# RiskChemi_Sensors_V2_11.net
KiCad netlist of a schematic drawn in Altium Designer
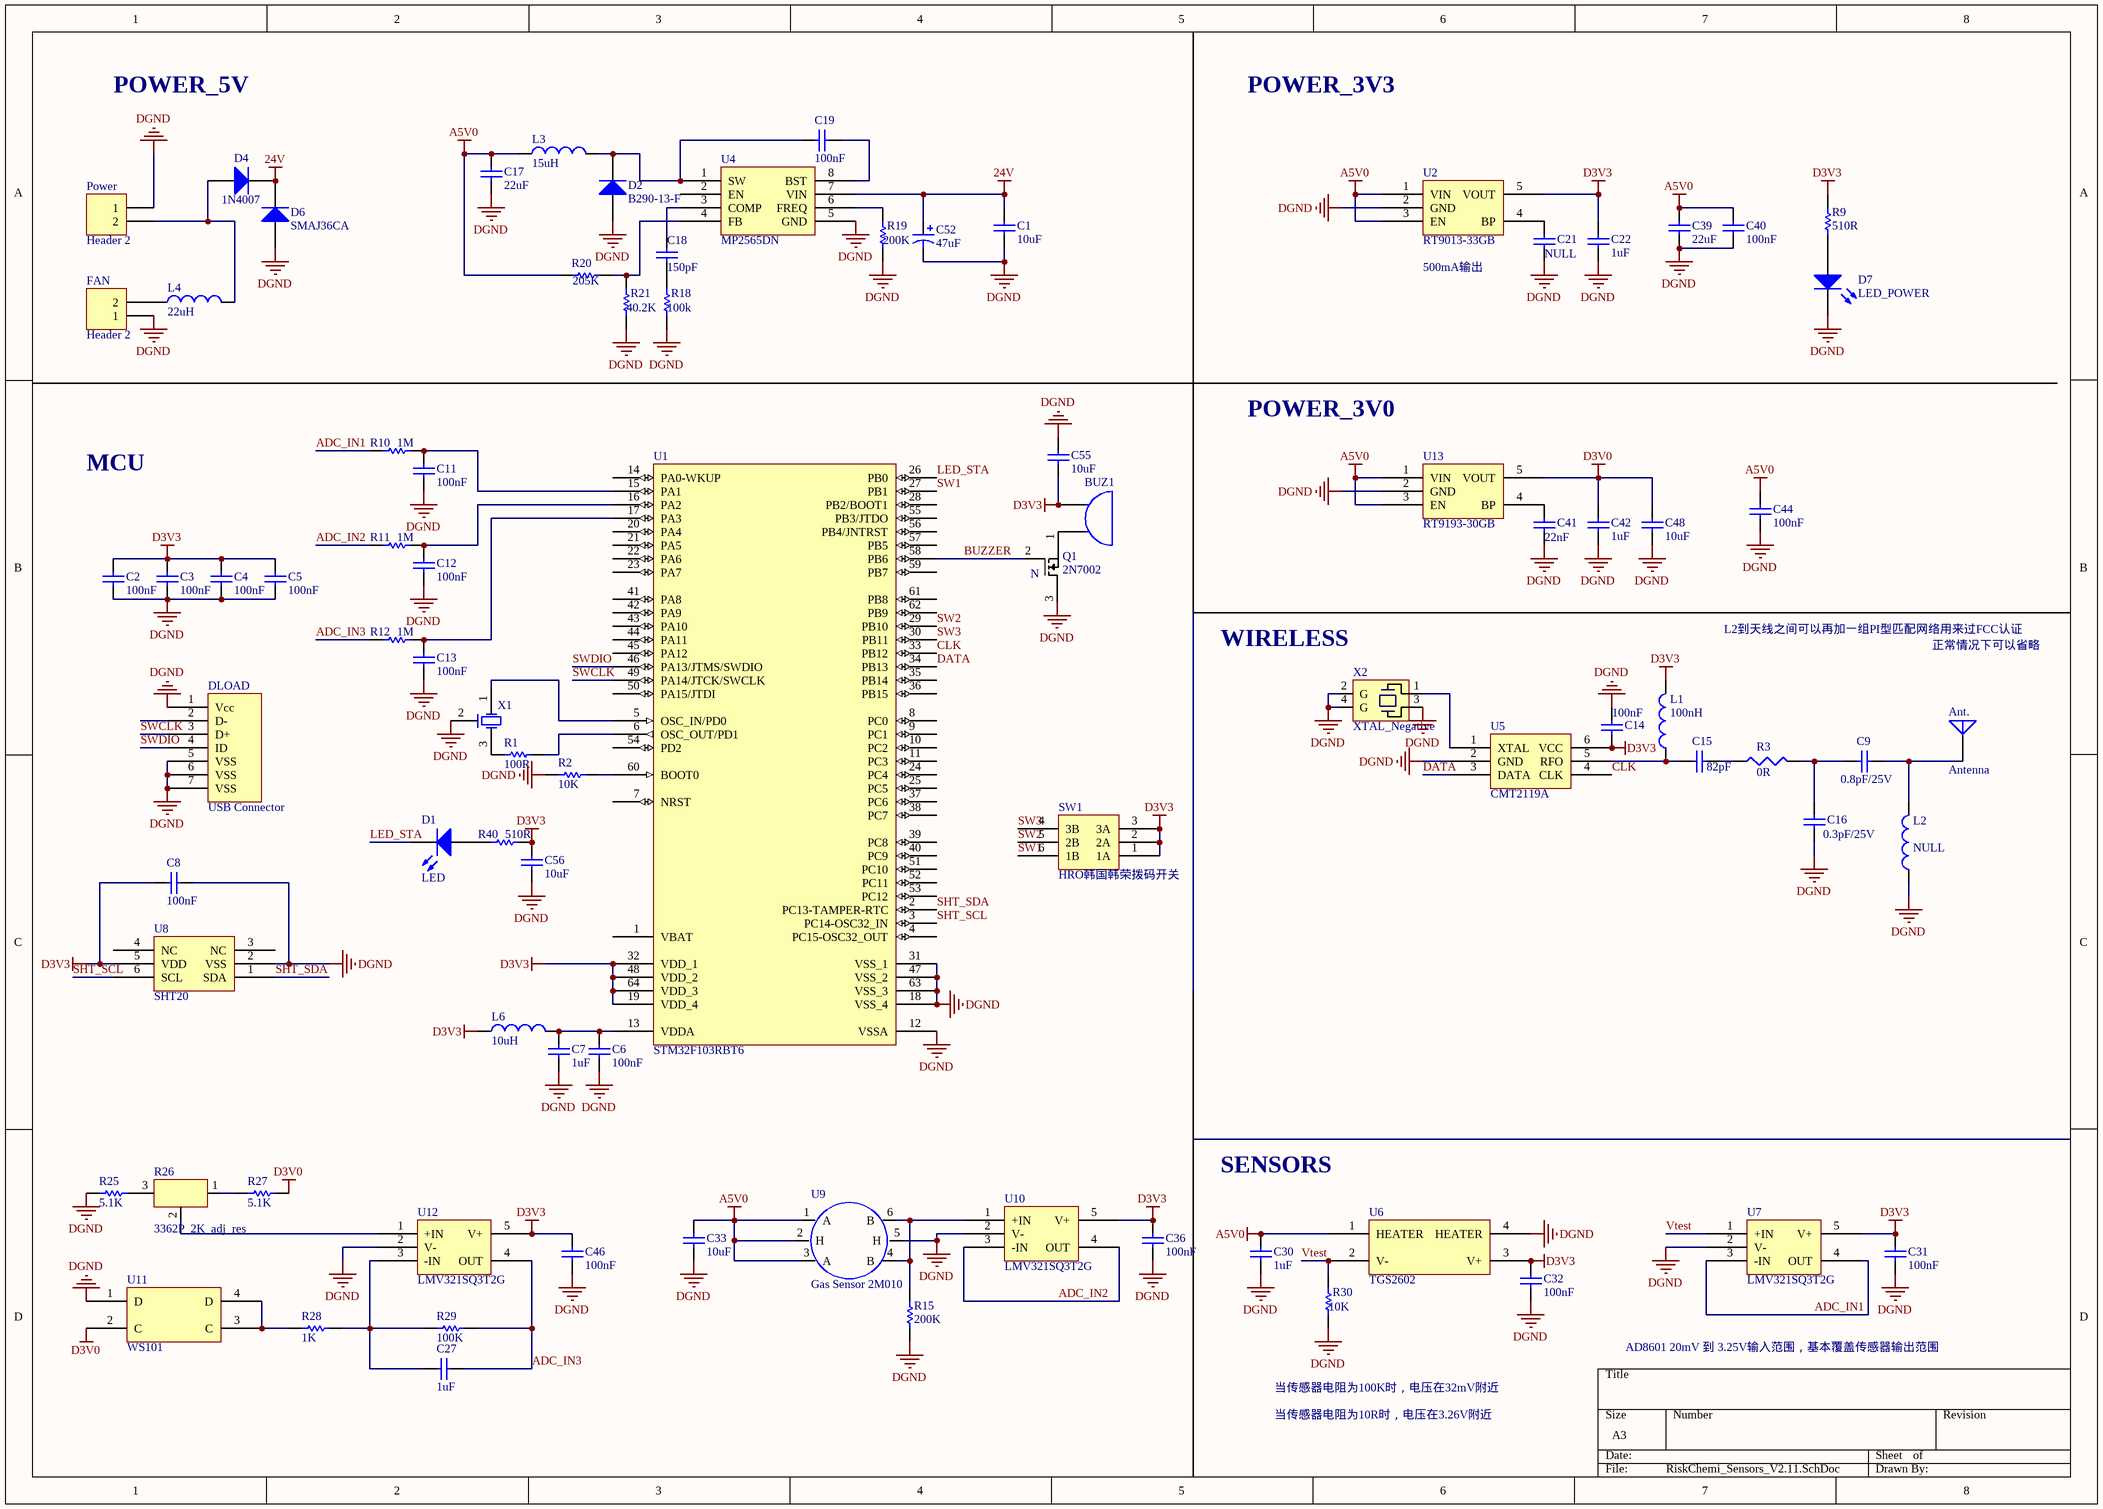
[diagram p0: RiskChemi_Sensors_V2.11.SchDoc]

(export (version "E")
  (design (tool "Eeschema 10.0.6"))
  (components
    (comp (ref "Ant.")
      (value "Antenna")
      (footprint "PIN1")
      (description "Generic Antenna")
      (fields (field (name "PUBLISHER") "Altium Limited"))
      (libsource (lib "Miscellaneous Devices") (part "Antenna"))
    )
    (comp (ref "BUZ1")
      (value "BUZZER 0905 through hole")
      (footprint "BUZ0905")
      (description "Buzzer")
      (libsource (lib "杂元件库") (part "BUZZER"))
    )
    (comp (ref "C1")
      (value "10uF")
      (footprint "0805")
      (description "Capacitor,50V")
      (fields (field (name "PUBLISHER") "Altium Limited"))
      (libsource (lib "Miscellaneous Devices") (part "Cap"))
    )
    (comp (ref "C2")
      (value "100nF")
      (footprint "BinFeng:0603")
      (description "Capacitor")
      (fields (field (name "PUBLISHER") "Altium Limited"))
      (libsource (lib "Miscellaneous Devices") (part "Cap"))
    )
    (comp (ref "C3")
      (value "100nF")
      (footprint "BinFeng:0603")
      (description "Capacitor")
      (fields (field (name "PUBLISHER") "Altium Limited"))
      (libsource (lib "Miscellaneous Devices") (part "Cap"))
    )
    (comp (ref "C4")
      (value "100nF")
      (footprint "BinFeng:0603")
      (description "Capacitor")
      (fields (field (name "PUBLISHER") "Altium Limited"))
      (libsource (lib "Miscellaneous Devices") (part "Cap"))
    )
    (comp (ref "C5")
      (value "100nF")
      (footprint "BinFeng:0603")
      (description "Capacitor")
      (fields (field (name "PUBLISHER") "Altium Limited"))
      (libsource (lib "Miscellaneous Devices") (part "Cap"))
    )
    (comp (ref "C6")
      (value "100nF")
      (footprint "BinFeng:0603")
      (description "Capacitor")
      (fields (field (name "PUBLISHER") "Altium Limited"))
      (libsource (lib "Miscellaneous Devices") (part "Cap"))
    )
    (comp (ref "C7")
      (value "1uF")
      (footprint "BinFeng:0603")
      (description "Capacitor")
      (fields (field (name "PUBLISHER") "Altium Limited"))
      (libsource (lib "Miscellaneous Devices") (part "Cap"))
    )
    (comp (ref "C8")
      (value "100nF")
      (footprint "BinFeng:0603")
      (description "Capacitor")
      (fields (field (name "PUBLISHER") "Altium Limited"))
      (libsource (lib "Miscellaneous Devices") (part "Cap"))
    )
    (comp (ref "C9")
      (value "0.8pF/25V")
      (footprint "1608[0603]")
      (description "Capacitor (Semiconductor SIM Model)")
      (fields (field (name "PUBLISHER") "Altium Limited"))
      (libsource (lib "Miscellaneous Devices") (part "Cap Semi"))
    )
    (comp (ref "C11")
      (value "100nF")
      (footprint "BinFeng:0603")
      (description "Capacitor")
      (fields (field (name "PUBLISHER") "Altium Limited"))
      (libsource (lib "Miscellaneous Devices") (part "Cap"))
    )
    (comp (ref "C12")
      (value "100nF")
      (footprint "BinFeng:0603")
      (description "Capacitor")
      (fields (field (name "PUBLISHER") "Altium Limited"))
      (libsource (lib "Miscellaneous Devices") (part "Cap"))
    )
    (comp (ref "C13")
      (value "100nF")
      (footprint "BinFeng:0603")
      (description "Capacitor")
      (fields (field (name "PUBLISHER") "Altium Limited"))
      (libsource (lib "Miscellaneous Devices") (part "Cap"))
    )
    (comp (ref "C14")
      (value "100nF")
      (footprint "BinFeng:0402")
      (description "Capacitor")
      (fields (field (name "PUBLISHER") "Altium Limited"))
      (libsource (lib "Miscellaneous Devices") (part "Cap"))
    )
    (comp (ref "C15")
      (value "82pF")
      (footprint "BinFeng:0402")
      (description "Capacitor")
      (fields (field (name "PUBLISHER") "Altium Limited"))
      (libsource (lib "Miscellaneous Devices") (part "Cap"))
    )
    (comp (ref "C16")
      (value "0.3pF/25V")
      (footprint "BinFeng:0402")
      (description "Capacitor")
      (fields (field (name "PUBLISHER") "Altium Limited"))
      (libsource (lib "Miscellaneous Devices") (part "Cap"))
    )
    (comp (ref "C17")
      (value "22uF")
      (footprint "0805")
      (description "Capacitor,50V")
      (fields (field (name "PUBLISHER") "Altium Limited"))
      (libsource (lib "Miscellaneous Devices") (part "Cap"))
    )
    (comp (ref "C18")
      (value "150pF")
      (footprint "BinFeng:0603")
      (description "Capacitor")
      (fields (field (name "PUBLISHER") "Altium Limited"))
      (libsource (lib "Miscellaneous Devices") (part "Cap"))
    )
    (comp (ref "C19")
      (value "100nF")
      (footprint "BinFeng:0603")
      (description "Capacitor")
      (fields (field (name "PUBLISHER") "Altium Limited"))
      (libsource (lib "Miscellaneous Devices") (part "Cap"))
    )
    (comp (ref "C21")
      (value "NULL")
      (footprint "BinFeng:0402")
      (description "Capacitor")
      (fields (field (name "PUBLISHER") "Altium Limited"))
      (libsource (lib "Miscellaneous Devices") (part "Cap"))
    )
    (comp (ref "C22")
      (value "1uF")
      (footprint "BinFeng:0402")
      (description "Capacitor")
      (fields (field (name "PUBLISHER") "Altium Limited"))
      (libsource (lib "Miscellaneous Devices") (part "Cap"))
    )
    (comp (ref "C27")
      (value "1uF")
      (footprint "BinFeng:0603")
      (description "Capacitor")
      (fields (field (name "PUBLISHER") "Altium Limited"))
      (libsource (lib "Miscellaneous Devices") (part "Cap"))
    )
    (comp (ref "C30")
      (value "1uF")
      (footprint "BinFeng:0603")
      (description "Capacitor")
      (fields (field (name "PUBLISHER") "Altium Limited"))
      (libsource (lib "Miscellaneous Devices") (part "Cap"))
    )
    (comp (ref "C31")
      (value "100nF")
      (footprint "BinFeng:0603")
      (description "Capacitor")
      (fields (field (name "PUBLISHER") "Altium Limited"))
      (libsource (lib "Miscellaneous Devices") (part "Cap"))
    )
    (comp (ref "C32")
      (value "100nF")
      (footprint "BinFeng:0603")
      (description "Capacitor")
      (fields (field (name "PUBLISHER") "Altium Limited"))
      (libsource (lib "Miscellaneous Devices") (part "Cap"))
    )
    (comp (ref "C33")
      (value "10uF")
      (footprint "0805")
      (description "Capacitor")
      (fields (field (name "PUBLISHER") "Altium Limited"))
      (libsource (lib "Miscellaneous Devices") (part "Cap"))
    )
    (comp (ref "C36")
      (value "100nF")
      (footprint "BinFeng:0603")
      (description "Capacitor")
      (fields (field (name "PUBLISHER") "Altium Limited"))
      (libsource (lib "Miscellaneous Devices") (part "Cap"))
    )
    (comp (ref "C39")
      (value "22uF")
      (footprint "1206")
      (description "Capacitor")
      (fields (field (name "PUBLISHER") "Altium Limited"))
      (libsource (lib "Miscellaneous Devices") (part "Cap"))
    )
    (comp (ref "C40")
      (value "100nF")
      (footprint "BinFeng:0402")
      (description "Capacitor")
      (fields (field (name "PUBLISHER") "Altium Limited"))
      (libsource (lib "Miscellaneous Devices") (part "Cap"))
    )
    (comp (ref "C41")
      (value "22nF")
      (footprint "BinFeng:0402")
      (description "Capacitor")
      (fields (field (name "PUBLISHER") "Altium Limited"))
      (libsource (lib "Miscellaneous Devices") (part "Cap"))
    )
    (comp (ref "C42")
      (value "1uF")
      (footprint "BinFeng:0402")
      (description "Capacitor")
      (fields (field (name "PUBLISHER") "Altium Limited"))
      (libsource (lib "Miscellaneous Devices") (part "Cap"))
    )
    (comp (ref "C44")
      (value "100nF")
      (footprint "BinFeng:0402")
      (description "Capacitor")
      (fields (field (name "PUBLISHER") "Altium Limited"))
      (libsource (lib "Miscellaneous Devices") (part "Cap"))
    )
    (comp (ref "C46")
      (value "100nF")
      (footprint "BinFeng:0603")
      (description "Capacitor")
      (fields (field (name "PUBLISHER") "Altium Limited"))
      (libsource (lib "Miscellaneous Devices") (part "Cap"))
    )
    (comp (ref "C48")
      (value "10uF")
      (footprint "0805")
      (description "Capacitor")
      (fields (field (name "PUBLISHER") "Altium Limited"))
      (libsource (lib "Miscellaneous Devices") (part "Cap"))
    )
    (comp (ref "C52")
      (value "47uF")
      (footprint "cap_pol_8*10.2")
      (description "Polarized Capacitor (Radial)")
      (fields (field (name "PUBLISHER") "Altium Limited"))
      (libsource (lib "Miscellaneous Devices") (part "Cap Pol1"))
    )
    (comp (ref "C55")
      (value "10uF")
      (footprint "0805")
      (description "Capacitor")
      (fields (field (name "PUBLISHER") "Altium Limited"))
      (libsource (lib "Miscellaneous Devices") (part "Cap"))
    )
    (comp (ref "C56")
      (value "10uF")
      (footprint "0805")
      (description "Capacitor")
      (fields (field (name "PUBLISHER") "Altium Limited"))
      (libsource (lib "Miscellaneous Devices") (part "Cap"))
    )
    (comp (ref "D1")
      (value "LED")
      (footprint "1206_LED")
      (description "Typical INFRARED GaAs LED")
      (fields (field (name "PUBLISHER") "Altium Limited"))
      (libsource (lib "Miscellaneous Devices") (part "LED0"))
    )
    (comp (ref "D2")
      (value "B290-13-F")
      (footprint "B290")
      (description "Default Diode")
      (fields (field (name "PUBLISHER") "Altium Limited"))
      (libsource (lib "Miscellaneous Devices") (part "Diode"))
    )
    (comp (ref "D4")
      (value "1N4007")
      (footprint "6032_pol")
      (description "1 Amp General Purpose Rectifier")
      (fields (field (name "PUBLISHER") "Altium Limited"))
      (libsource (lib "Miscellaneous Devices") (part "Diode 1N4007"))
    )
    (comp (ref "D6")
      (value "SMAJ36CA")
      (footprint "B290")
      (description "1 Amp General Purpose Rectifier")
      (fields (field (name "PUBLISHER") "Altium Limited"))
      (libsource (lib "Miscellaneous Devices") (part "Diode 1N4007"))
    )
    (comp (ref "D7")
      (value "LED_POWER")
      (footprint "1206_LED")
      (description "Typical INFRARED GaAs LED")
      (fields (field (name "PUBLISHER") "Altium Limited"))
      (libsource (lib "Miscellaneous Devices") (part "LED0"))
    )
    (comp (ref "DLOAD")
      (value "USB Connector")
      (footprint "Mini_USB")
      (libsource (lib "BinFeng_Connectors") (part "Component_1"))
    )
    (comp (ref "FAN")
      (value "Header 2")
      (footprint "HDR1X2")
      (description "Header, 2-Pin")
      (fields (field (name "PUBLISHER") "Altium Limited"))
      (libsource (lib "") (part "Header 2_1"))
    )
    (comp (ref "L1")
      (value "100nH")
      (footprint "0603C")
      (description "Inductor")
      (fields (field (name "PUBLISHER") "Altium Limited"))
      (libsource (lib "Miscellaneous Devices") (part "Inductor"))
    )
    (comp (ref "L2")
      (value "NULL")
      (footprint "hg:0402")
      (description "Inductor")
      (fields (field (name "PUBLISHER") "Altium Limited"))
      (libsource (lib "Miscellaneous Devices") (part "Inductor"))
    )
    (comp (ref "L3")
      (value "15uH")
      (footprint "4*4 Inductor")
      (description "Inductor, 1A")
      (fields (field (name "PUBLISHER") "Altium Limited"))
      (libsource (lib "Miscellaneous Devices") (part "Inductor"))
    )
    (comp (ref "L4")
      (value "22uH")
      (footprint "10*10Inductor")
      (description "Inductor, 1A")
      (fields (field (name "PUBLISHER") "Altium Limited"))
      (libsource (lib "Miscellaneous Devices") (part "Inductor"))
    )
    (comp (ref "L6")
      (value "10uH")
      (footprint "0805")
      (description "Inductor")
      (fields (field (name "PUBLISHER") "Altium Limited"))
      (libsource (lib "Miscellaneous Devices") (part "Inductor"))
    )
    (comp (ref "Power")
      (value "Header 2")
      (footprint "HDR1X2")
      (description "Header, 2-Pin")
      (fields (field (name "PUBLISHER") "Altium Limited"))
      (libsource (lib "Miscellaneous Connectors") (part "Header 2"))
    )
    (comp (ref "Q1") (value "2N7002") (footprint "2N7002") (libsource (lib "seeder") (part "N-MOSFET")))
    (comp (ref "R1")
      (value "100R")
      (footprint "BinFeng:0603")
      (description "Resistor")
      (fields (field (name "PUBLISHER") "Altium Limited"))
      (libsource (lib "Miscellaneous Devices") (part "Res1"))
    )
    (comp (ref "R2")
      (value "10K")
      (footprint "BinFeng:0603")
      (description "Resistor")
      (fields (field (name "PUBLISHER") "Altium Limited"))
      (libsource (lib "Miscellaneous Devices") (part "Res1"))
    )
    (comp (ref "R3")
      (value "0R")
      (footprint "J1-0603")
      (description "Resistor")
      (fields (field (name "PUBLISHER") "Altium Limited"))
      (libsource (lib "Miscellaneous Devices") (part "Res3"))
    )
    (comp (ref "R9")
      (value "510R")
      (footprint "BinFeng:0603")
      (description "Resistor")
      (fields (field (name "PUBLISHER") "Altium Limited"))
      (libsource (lib "Miscellaneous Devices") (part "Res1"))
    )
    (comp (ref "R10")
      (value "1M")
      (footprint "BinFeng:0603")
      (description "Resistor")
      (fields (field (name "PUBLISHER") "Altium Limited"))
      (libsource (lib "Miscellaneous Devices") (part "Res1"))
    )
    (comp (ref "R11")
      (value "1M")
      (footprint "BinFeng:0603")
      (description "Resistor")
      (fields (field (name "PUBLISHER") "Altium Limited"))
      (libsource (lib "Miscellaneous Devices") (part "Res1"))
    )
    (comp (ref "R12")
      (value "1M")
      (footprint "BinFeng:0603")
      (description "Resistor")
      (fields (field (name "PUBLISHER") "Altium Limited"))
      (libsource (lib "Miscellaneous Devices") (part "Res1"))
    )
    (comp (ref "R15")
      (value "200K")
      (footprint "BinFeng:0603C")
      (description "Resistor")
      (fields (field (name "Comment") "Res1") (field (name "PUBLISHER") "Altium Limited"))
      (libsource (lib "Miscellaneous Devices") (part "Res1"))
    )
    (comp (ref "R18")
      (value "100k")
      (footprint "BinFeng:0603")
      (description "Resistor")
      (fields (field (name "PUBLISHER") "Altium Limited"))
      (libsource (lib "Miscellaneous Devices") (part "Res1"))
    )
    (comp (ref "R19")
      (value "200K")
      (footprint "BinFeng:0402")
      (description "Resistor")
      (fields (field (name "PUBLISHER") "Altium Limited"))
      (libsource (lib "Miscellaneous Devices") (part "Res1"))
    )
    (comp (ref "R20")
      (value "205K")
      (footprint "BinFeng:0603")
      (description "Resistor")
      (fields (field (name "PUBLISHER") "Altium Limited"))
      (libsource (lib "Miscellaneous Devices") (part "Res1"))
    )
    (comp (ref "R21")
      (value "40.2K")
      (footprint "BinFeng:0603")
      (description "Resistor")
      (fields (field (name "PUBLISHER") "Altium Limited"))
      (libsource (lib "Miscellaneous Devices") (part "Res1"))
    )
    (comp (ref "R25")
      (value "5.1K")
      (footprint "BinFeng:0603")
      (description "Resistor")
      (fields (field (name "PUBLISHER") "Altium Limited"))
      (libsource (lib "Miscellaneous Devices") (part "Res1"))
    )
    (comp (ref "R26")
      (value "3362P_2K_adj_res")
      (footprint "res_adj")
      (libsource (lib "BinFeng_IC") (part "res_adj"))
    )
    (comp (ref "R27")
      (value "5.1K")
      (footprint "BinFeng:0603")
      (description "Resistor")
      (fields (field (name "PUBLISHER") "Altium Limited"))
      (libsource (lib "Miscellaneous Devices") (part "Res1"))
    )
    (comp (ref "R28")
      (value "1K")
      (footprint "BinFeng:0603")
      (description "Resistor")
      (fields (field (name "PUBLISHER") "Altium Limited"))
      (libsource (lib "Miscellaneous Devices") (part "Res1"))
    )
    (comp (ref "R29")
      (value "100K")
      (footprint "BinFeng:0603")
      (description "Resistor")
      (fields (field (name "PUBLISHER") "Altium Limited"))
      (libsource (lib "Miscellaneous Devices") (part "Res1"))
    )
    (comp (ref "R30")
      (value "10K")
      (footprint "BinFeng:0603")
      (description "Resistor")
      (fields (field (name "PUBLISHER") "Altium Limited"))
      (libsource (lib "Miscellaneous Devices") (part "Res1"))
    )
    (comp (ref "R40")
      (value "510R")
      (footprint "BinFeng:0603")
      (description "Resistor")
      (fields (field (name "PUBLISHER") "Altium Limited"))
      (libsource (lib "Miscellaneous Devices") (part "Res1"))
    )
    (comp (ref "SW1")
      (value "HRO韩国韩荣拨码开关")
      (footprint "SW_6P_HRO")
      (libsource (lib "BinFeng_IC") (part "SW_6P"))
    )
    (comp (ref "U1")
      (value "STM32F103RBT6")
      (footprint "LQFP64_N")
      (description "STM32 ARM-based 32-bit MCU with 64 Kbytes Flash, 64-pin LQFP, Industrial Temperature")
      (fields (field (name "PUBLISHER") "Altium Limited"))
      (libsource (lib "ST Microcontroller 32-Bit STM32") (part "STM32F103R8T6"))
    )
    (comp (ref "U2")
      (value "RT9013-33GB")
      (footprint "SOT-23-5")
      (libsource (lib "BinFeng_IC") (part "RT9193"))
    )
    (comp (ref "U4")
      (value "MP2565DN")
      (footprint "so-8")
      (description "DCDC 4.5V~28V input 1.8V ~5V output low power")
      (libsource (lib "BinFeng_IC") (part "MP1584"))
    )
    (comp (ref "U5")
      (value "CMT2119A")
      (footprint "sot23-6")
      (libsource (lib "BinFeng_IC") (part "CMT2119A"))
    )
    (comp (ref "U6")
      (value "TGS2602")
      (footprint "Gas Sensor TGS2602 Slot")
      (description "VOC sensor")
      (libsource (lib "BinFeng_IC") (part "TGS2602"))
    )
    (comp (ref "U7")
      (value "LMV321SQ3T2G")
      (footprint "SC-70-5")
      (libsource (lib "BinFeng_IC") (part "LMV321SQ3T2G"))
    )
    (comp (ref "U8") (value "SHT20") (footprint "SHT20") (libsource (lib "BinFeng_IC") (part "SHT20")))
    (comp (ref "U9")
      (value "Gas Sensor 2M010")
      (footprint "Gas Sensor 2M010 Slot")
      (libsource (lib "BinFeng_IC") (part "Gas Sensor"))
    )
    (comp (ref "U10")
      (value "LMV321SQ3T2G")
      (footprint "SC-70-5")
      (libsource (lib "BinFeng_IC") (part "LMV321SQ3T2G"))
    )
    (comp (ref "U11")
      (value "WS101")
      (footprint "Gas_Sensor_WS101_Slot")
      (libsource (lib "BinFeng_IC") (part "Gas Sensor_WS101"))
    )
    (comp (ref "U12")
      (value "LMV321SQ3T2G")
      (footprint "SC-70-5")
      (libsource (lib "BinFeng_IC") (part "LMV321SQ3T2G"))
    )
    (comp (ref "U13")
      (value "RT9193-30GB")
      (footprint "SOT-23-5")
      (libsource (lib "BinFeng_IC") (part "RT9193"))
    )
    (comp (ref "X1") (value "8M smd") (footprint "8Mhz_XTAL") (libsource (lib "Schlib1") (part "8M smd")))
    (comp (ref "X2")
      (value "XTAL_Negative")
      (footprint "XTAL3225")
      (libsource (lib "BinFeng_IC") (part "XTAL_Negative"))
    )
  )
  (nets
    (net (code "1") (name "/ADC_IN1") (class "Default")
      (node (ref "R10") (pin "1") (pinfunction "1_1") (pintype "passive"))
      (node (ref "U7") (pin "3") (pinfunction "-IN_3") (pintype "passive"))
      (node (ref "U7") (pin "4") (pinfunction "OUT_4") (pintype "passive"))
    )
    (net (code "2") (name "/ADC_IN2") (class "Default")
      (node (ref "R11") (pin "1") (pinfunction "1_1") (pintype "passive"))
      (node (ref "U10") (pin "3") (pinfunction "-IN_3") (pintype "passive"))
      (node (ref "U10") (pin "4") (pinfunction "OUT_4") (pintype "passive"))
    )
    (net (code "3") (name "/ADC_IN3") (class "Default")
      (node (ref "C27") (pin "1") (pinfunction "1_1") (pintype "passive"))
      (node (ref "R12") (pin "1") (pinfunction "1_1") (pintype "passive"))
      (node (ref "R29") (pin "2") (pinfunction "2_2") (pintype "passive"))
      (node (ref "U12") (pin "4") (pinfunction "OUT_4") (pintype "passive"))
    )
    (net (code "4") (name "/BUZZER") (class "Default")
      (node (ref "Q1") (pin "2") (pinfunction "G_2") (pintype "passive"))
      (node (ref "U1") (pin "58") (pinfunction "PB6_58") (pintype "bidirectional"))
    )
    (net (code "5") (name "/CLK") (class "Default")
      (node (ref "U1") (pin "33") (pinfunction "PB12_33") (pintype "bidirectional"))
      (node (ref "U5") (pin "4") (pinfunction "CLK_4") (pintype "passive"))
    )
    (net (code "6") (name "/DATA") (class "Default")
      (node (ref "U1") (pin "34") (pinfunction "PB13_34") (pintype "bidirectional"))
      (node (ref "U5") (pin "3") (pinfunction "DATA_3") (pintype "passive"))
    )
    (net (code "7") (name "/LED_STA") (class "Default")
      (node (ref "D1") (pin "2") (pinfunction "K_2") (pintype "passive"))
      (node (ref "U1") (pin "26") (pinfunction "PB0_26") (pintype "bidirectional"))
    )
    (net (code "8") (name "/SHT_SCL") (class "Default")
      (node (ref "U1") (pin "3") (pinfunction "PC14-OSC32_IN_3") (pintype "bidirectional"))
      (node (ref "U8") (pin "6") (pinfunction "SCL_6") (pintype "passive"))
    )
    (net (code "9") (name "/SHT_SDA") (class "Default")
      (node (ref "U1") (pin "2") (pinfunction "PC13-TAMPER-RTC_2") (pintype "bidirectional"))
      (node (ref "U8") (pin "1") (pinfunction "SDA_1") (pintype "passive"))
    )
    (net (code "10") (name "/SW1") (class "Default")
      (node (ref "SW1") (pin "6") (pinfunction "1B_6") (pintype "passive"))
      (node (ref "U1") (pin "27") (pinfunction "PB1_27") (pintype "bidirectional"))
    )
    (net (code "11") (name "/SW2") (class "Default")
      (node (ref "SW1") (pin "5") (pinfunction "2B_5") (pintype "passive"))
      (node (ref "U1") (pin "29") (pinfunction "PB10_29") (pintype "bidirectional"))
    )
    (net (code "12") (name "/SW3") (class "Default")
      (node (ref "SW1") (pin "4") (pinfunction "3B_4") (pintype "passive"))
      (node (ref "U1") (pin "30") (pinfunction "PB11_30") (pintype "bidirectional"))
    )
    (net (code "13") (name "/SWCLK") (class "Default")
      (node (ref "DLOAD") (pin "3") (pinfunction "D+_3") (pintype "passive"))
      (node (ref "U1") (pin "49") (pinfunction "PA14/JTCK/SWCLK_49") (pintype "bidirectional"))
    )
    (net (code "14") (name "/SWDIO") (class "Default")
      (node (ref "DLOAD") (pin "4") (pinfunction "ID_4") (pintype "passive"))
      (node (ref "U1") (pin "46") (pinfunction "PA13/JTMS/SWDIO_46") (pintype "bidirectional"))
    )
    (net (code "15") (name "/Vtest") (class "Default")
      (node (ref "R30") (pin "2") (pinfunction "2_2") (pintype "passive"))
      (node (ref "U6") (pin "2") (pinfunction "V-_2") (pintype "passive"))
      (node (ref "U7") (pin "1") (pinfunction "+IN_1") (pintype "passive"))
    )
    (net (code "16") (name "24V") (class "Default")
      (node (ref "C1") (pin "2") (pinfunction "2_2") (pintype "passive"))
      (node (ref "C52") (pin "1") (pinfunction "1_1") (pintype "passive"))
      (node (ref "D4") (pin "2") (pinfunction "K_2") (pintype "passive"))
      (node (ref "D6") (pin "2") (pinfunction "K_2") (pintype "passive"))
      (node (ref "U4") (pin "7") (pinfunction "VIN_7") (pintype "passive"))
    )
    (net (code "17") (name "A5V0") (class "Default")
      (node (ref "C17") (pin "2") (pinfunction "2_2") (pintype "passive"))
      (node (ref "C30") (pin "2") (pinfunction "2_2") (pintype "passive"))
      (node (ref "C33") (pin "2") (pinfunction "2_2") (pintype "passive"))
      (node (ref "C39") (pin "1") (pinfunction "1_1") (pintype "passive"))
      (node (ref "C40") (pin "2") (pinfunction "2_2") (pintype "passive"))
      (node (ref "C44") (pin "2") (pinfunction "2_2") (pintype "passive"))
      (node (ref "L3") (pin "1") (pinfunction "1_1") (pintype "passive"))
      (node (ref "R20") (pin "2") (pinfunction "2_2") (pintype "passive"))
      (node (ref "U13") (pin "1") (pinfunction "VIN_1") (pintype "passive"))
      (node (ref "U13") (pin "3") (pinfunction "EN_3") (pintype "passive"))
      (node (ref "U2") (pin "1") (pinfunction "VIN_1") (pintype "passive"))
      (node (ref "U2") (pin "3") (pinfunction "EN_3") (pintype "passive"))
      (node (ref "U6") (pin "1") (pinfunction "HEATER_1") (pintype "passive"))
      (node (ref "U9") (pin "1") (pinfunction "A_1") (pintype "passive"))
      (node (ref "U9") (pin "2") (pinfunction "H_2") (pintype "passive"))
      (node (ref "U9") (pin "3") (pinfunction "A_3") (pintype "passive"))
    )
    (net (code "18") (name "D3V0") (class "Default")
      (node (ref "C42") (pin "2") (pinfunction "2_2") (pintype "passive"))
      (node (ref "C48") (pin "2") (pinfunction "2_2") (pintype "passive"))
      (node (ref "R27") (pin "2") (pinfunction "2_2") (pintype "passive"))
      (node (ref "U11") (pin "2") (pinfunction "C_2") (pintype "passive"))
      (node (ref "U13") (pin "5") (pinfunction "VOUT_5") (pintype "passive"))
    )
    (net (code "19") (name "D3V3") (class "Default")
      (node (ref "BUZ1") (pin "1") (pinfunction "A_1") (pintype "passive"))
      (node (ref "C14") (pin "2") (pinfunction "2_2") (pintype "passive"))
      (node (ref "C2") (pin "2") (pinfunction "2_2") (pintype "passive"))
      (node (ref "C22") (pin "2") (pinfunction "2_2") (pintype "passive"))
      (node (ref "C3") (pin "2") (pinfunction "2_2") (pintype "passive"))
      (node (ref "C31") (pin "2") (pinfunction "2_2") (pintype "passive"))
      (node (ref "C32") (pin "2") (pinfunction "2_2") (pintype "passive"))
      (node (ref "C36") (pin "2") (pinfunction "2_2") (pintype "passive"))
      (node (ref "C4") (pin "2") (pinfunction "2_2") (pintype "passive"))
      (node (ref "C46") (pin "2") (pinfunction "2_2") (pintype "passive"))
      (node (ref "C5") (pin "2") (pinfunction "2_2") (pintype "passive"))
      (node (ref "C55") (pin "2") (pinfunction "2_2") (pintype "passive"))
      (node (ref "C56") (pin "2") (pinfunction "2_2") (pintype "passive"))
      (node (ref "C8") (pin "2") (pinfunction "2_2") (pintype "passive"))
      (node (ref "L1") (pin "2") (pinfunction "2_2") (pintype "passive"))
      (node (ref "L6") (pin "1") (pinfunction "1_1") (pintype "passive"))
      (node (ref "R40") (pin "2") (pinfunction "2_2") (pintype "passive"))
      (node (ref "R9") (pin "2") (pinfunction "2_2") (pintype "passive"))
      (node (ref "SW1") (pin "1") (pinfunction "1A_1") (pintype "passive"))
      (node (ref "SW1") (pin "2") (pinfunction "2A_2") (pintype "passive"))
      (node (ref "SW1") (pin "3") (pinfunction "3A_3") (pintype "passive"))
      (node (ref "U1") (pin "19") (pinfunction "VDD_4_19") (pintype "power_in"))
      (node (ref "U1") (pin "32") (pinfunction "VDD_1_32") (pintype "power_in"))
      (node (ref "U1") (pin "48") (pinfunction "VDD_2_48") (pintype "power_in"))
      (node (ref "U1") (pin "64") (pinfunction "VDD_3_64") (pintype "power_in"))
      (node (ref "U10") (pin "5") (pinfunction "V+_5") (pintype "passive"))
      (node (ref "U12") (pin "5") (pinfunction "V+_5") (pintype "passive"))
      (node (ref "U2") (pin "5") (pinfunction "VOUT_5") (pintype "passive"))
      (node (ref "U5") (pin "6") (pinfunction "VCC_6") (pintype "passive"))
      (node (ref "U6") (pin "3") (pinfunction "V+_3") (pintype "passive"))
      (node (ref "U7") (pin "5") (pinfunction "V+_5") (pintype "passive"))
      (node (ref "U8") (pin "5") (pinfunction "VDD_5") (pintype "passive"))
    )
    (net (code "20") (name "DGND") (class "Default")
      (node (ref "C1") (pin "1") (pinfunction "1_1") (pintype "passive"))
      (node (ref "C11") (pin "2") (pinfunction "2_2") (pintype "passive"))
      (node (ref "C12") (pin "1") (pinfunction "1_1") (pintype "passive"))
      (node (ref "C13") (pin "1") (pinfunction "1_1") (pintype "passive"))
      (node (ref "C14") (pin "1") (pinfunction "1_1") (pintype "passive"))
      (node (ref "C16") (pin "1") (pinfunction "1_1") (pintype "passive"))
      (node (ref "C17") (pin "1") (pinfunction "1_1") (pintype "passive"))
      (node (ref "C2") (pin "1") (pinfunction "1_1") (pintype "passive"))
      (node (ref "C21") (pin "1") (pinfunction "1_1") (pintype "passive"))
      (node (ref "C22") (pin "1") (pinfunction "1_1") (pintype "passive"))
      (node (ref "C3") (pin "1") (pinfunction "1_1") (pintype "passive"))
      (node (ref "C30") (pin "1") (pinfunction "1_1") (pintype "passive"))
      (node (ref "C31") (pin "1") (pinfunction "1_1") (pintype "passive"))
      (node (ref "C32") (pin "1") (pinfunction "1_1") (pintype "passive"))
      (node (ref "C33") (pin "1") (pinfunction "1_1") (pintype "passive"))
      (node (ref "C36") (pin "1") (pinfunction "1_1") (pintype "passive"))
      (node (ref "C39") (pin "2") (pinfunction "2_2") (pintype "passive"))
      (node (ref "C4") (pin "1") (pinfunction "1_1") (pintype "passive"))
      (node (ref "C40") (pin "1") (pinfunction "1_1") (pintype "passive"))
      (node (ref "C41") (pin "1") (pinfunction "1_1") (pintype "passive"))
      (node (ref "C42") (pin "1") (pinfunction "1_1") (pintype "passive"))
      (node (ref "C44") (pin "1") (pinfunction "1_1") (pintype "passive"))
      (node (ref "C46") (pin "1") (pinfunction "1_1") (pintype "passive"))
      (node (ref "C48") (pin "1") (pinfunction "1_1") (pintype "passive"))
      (node (ref "C5") (pin "1") (pinfunction "1_1") (pintype "passive"))
      (node (ref "C52") (pin "2") (pinfunction "2_2") (pintype "passive"))
      (node (ref "C55") (pin "1") (pinfunction "1_1") (pintype "passive"))
      (node (ref "C56") (pin "1") (pinfunction "1_1") (pintype "passive"))
      (node (ref "C6") (pin "1") (pinfunction "1_1") (pintype "passive"))
      (node (ref "C7") (pin "1") (pinfunction "1_1") (pintype "passive"))
      (node (ref "C8") (pin "1") (pinfunction "1_1") (pintype "passive"))
      (node (ref "D2") (pin "1") (pinfunction "A_1") (pintype "passive"))
      (node (ref "D6") (pin "1") (pinfunction "A_1") (pintype "passive"))
      (node (ref "D7") (pin "2") (pinfunction "K_2") (pintype "passive"))
      (node (ref "DLOAD") (pin "1") (pinfunction "Vcc_1") (pintype "passive"))
      (node (ref "DLOAD") (pin "5") (pinfunction "VSS_5") (pintype "passive"))
      (node (ref "DLOAD") (pin "6") (pinfunction "VSS_6") (pintype "passive"))
      (node (ref "DLOAD") (pin "7") (pinfunction "VSS_7") (pintype "passive"))
      (node (ref "FAN") (pin "1") (pinfunction "1_1") (pintype "passive"))
      (node (ref "L2") (pin "1") (pinfunction "1_1") (pintype "passive"))
      (node (ref "Power") (pin "1") (pinfunction "1_1") (pintype "passive"))
      (node (ref "Q1") (pin "3") (pinfunction "S_3") (pintype "passive"))
      (node (ref "R15") (pin "2") (pinfunction "2_2") (pintype "passive"))
      (node (ref "R18") (pin "1") (pinfunction "1_1") (pintype "passive"))
      (node (ref "R19") (pin "1") (pinfunction "1_1") (pintype "passive"))
      (node (ref "R2") (pin "1") (pinfunction "1_1") (pintype "passive"))
      (node (ref "R21") (pin "1") (pinfunction "1_1") (pintype "passive"))
      (node (ref "R25") (pin "1") (pinfunction "1_1") (pintype "passive"))
      (node (ref "R30") (pin "1") (pinfunction "1_1") (pintype "passive"))
      (node (ref "U1") (pin "12") (pinfunction "VSSA_12") (pintype "power_in"))
      (node (ref "U1") (pin "18") (pinfunction "VSS_4_18") (pintype "power_in"))
      (node (ref "U1") (pin "31") (pinfunction "VSS_1_31") (pintype "power_in"))
      (node (ref "U1") (pin "47") (pinfunction "VSS_2_47") (pintype "power_in"))
      (node (ref "U1") (pin "63") (pinfunction "VSS_3_63") (pintype "power_in"))
      (node (ref "U10") (pin "2") (pinfunction "V-_2") (pintype "passive"))
      (node (ref "U11") (pin "1") (pinfunction "D_1") (pintype "passive"))
      (node (ref "U12") (pin "2") (pinfunction "V-_2") (pintype "passive"))
      (node (ref "U13") (pin "2") (pinfunction "GND_2") (pintype "passive"))
      (node (ref "U2") (pin "2") (pinfunction "GND_2") (pintype "passive"))
      (node (ref "U4") (pin "5") (pinfunction "GND_5") (pintype "passive"))
      (node (ref "U5") (pin "2") (pinfunction "GND_2") (pintype "passive"))
      (node (ref "U6") (pin "4") (pinfunction "HEATER_4") (pintype "passive"))
      (node (ref "U7") (pin "2") (pinfunction "V-_2") (pintype "passive"))
      (node (ref "U8") (pin "2") (pinfunction "VSS_2") (pintype "passive"))
      (node (ref "U9") (pin "5") (pinfunction "H_5") (pintype "passive"))
      (node (ref "X1") (pin "2") (pinfunction "GND_2") (pintype "passive"))
      (node (ref "X2") (pin "2") (pinfunction "G_2") (pintype "passive"))
      (node (ref "X2") (pin "3") (pintype "passive"))
      (node (ref "X2") (pin "4") (pinfunction "G_4") (pintype "passive"))
    )
    (net (code "21") (name "Net-(Ant.-A)") (class "Default")
      (node (ref "Ant.") (pin "1") (pinfunction "A_1") (pintype "passive"))
      (node (ref "C9") (pin "2") (pinfunction "2_2") (pintype "passive"))
      (node (ref "L2") (pin "2") (pinfunction "2_2") (pintype "passive"))
    )
    (net (code "22") (name "Net-(BUZ1-B)") (class "Default")
      (node (ref "BUZ1") (pin "2") (pinfunction "B_2") (pintype "passive"))
      (node (ref "Q1") (pin "1") (pinfunction "D_1") (pintype "passive"))
    )
    (net (code "23") (name "Net-(C15-Pad2)") (class "Default")
      (node (ref "C15") (pin "2") (pinfunction "2_2") (pintype "passive"))
      (node (ref "R3") (pin "1") (pinfunction "1_1") (pintype "passive"))
    )
    (net (code "24") (name "Net-(C16-Pad2)") (class "Default")
      (node (ref "C16") (pin "2") (pinfunction "2_2") (pintype "passive"))
      (node (ref "C9") (pin "1") (pinfunction "1_1") (pintype "passive"))
      (node (ref "R3") (pin "2") (pinfunction "2_2") (pintype "passive"))
    )
    (net (code "25") (name "Net-(C18-Pad2)") (class "Default")
      (node (ref "C18") (pin "2") (pinfunction "2_2") (pintype "passive"))
      (node (ref "R18") (pin "2") (pinfunction "2_2") (pintype "passive"))
    )
    (net (code "26") (name "Net-(D1-A)") (class "Default")
      (node (ref "D1") (pin "1") (pinfunction "A_1") (pintype "passive"))
      (node (ref "R40") (pin "1") (pinfunction "1_1") (pintype "passive"))
    )
    (net (code "27") (name "Net-(D2-K)") (class "Default")
      (node (ref "C19") (pin "2") (pinfunction "2_2") (pintype "passive"))
      (node (ref "D2") (pin "2") (pinfunction "K_2") (pintype "passive"))
      (node (ref "L3") (pin "2") (pinfunction "2_2") (pintype "passive"))
      (node (ref "U4") (pin "1") (pinfunction "SW_1") (pintype "passive"))
    )
    (net (code "28") (name "Net-(D4-A)") (class "Default")
      (node (ref "D4") (pin "1") (pinfunction "A_1") (pintype "passive"))
      (node (ref "L4") (pin "2") (pinfunction "2_2") (pintype "passive"))
      (node (ref "Power") (pin "2") (pinfunction "2_2") (pintype "passive"))
    )
    (net (code "29") (name "Net-(D7-A)") (class "Default")
      (node (ref "D7") (pin "1") (pinfunction "A_1") (pintype "passive"))
      (node (ref "R9") (pin "1") (pinfunction "1_1") (pintype "passive"))
    )
    (net (code "30") (name "Net-(FAN-Pad2)") (class "Default")
      (node (ref "FAN") (pin "2") (pinfunction "2_2") (pintype "passive"))
      (node (ref "L4") (pin "1") (pinfunction "1_1") (pintype "passive"))
    )
    (net (code "31") (name "Net-(R25-Pad2)") (class "Default")
      (node (ref "R25") (pin "2") (pinfunction "2_2") (pintype "passive"))
      (node (ref "R26") (pin "3") (pintype "passive"))
    )
    (net (code "32") (name "Net-(R26-Pad1)") (class "Default")
      (node (ref "R26") (pin "1") (pintype "passive"))
      (node (ref "R27") (pin "1") (pinfunction "1_1") (pintype "passive"))
    )
    (net (code "33") (name "Net-(R28-Pad1)") (class "Default")
      (node (ref "R28") (pin "1") (pinfunction "1_1") (pintype "passive"))
      (node (ref "U11") (pin "3") (pinfunction "C_3") (pintype "passive"))
      (node (ref "U11") (pin "4") (pinfunction "D_4") (pintype "passive"))
    )
    (net (code "34") (name "Net-(U1-BOOT0)") (class "Default")
      (node (ref "R2") (pin "2") (pinfunction "2_2") (pintype "passive"))
      (node (ref "U1") (pin "60") (pinfunction "BOOT0_60") (pintype "input"))
    )
    (net (code "35") (name "Net-(U1-OSC_IN{slash}PD0)") (class "Default")
      (node (ref "U1") (pin "5") (pinfunction "OSC_IN/PD0_5") (pintype "input"))
      (node (ref "X1") (pin "1") (pinfunction "OSC1_1") (pintype "passive"))
    )
    (net (code "36") (name "Net-(U1-OSC_OUT{slash}PD1)") (class "Default")
      (node (ref "R1") (pin "2") (pinfunction "2_2") (pintype "passive"))
      (node (ref "U1") (pin "6") (pinfunction "OSC_OUT/PD1_6") (pintype "output"))
    )
    (net (code "37") (name "Net-(U1-PA1)") (class "Default")
      (node (ref "C11") (pin "1") (pinfunction "1_1") (pintype "passive"))
      (node (ref "R10") (pin "2") (pinfunction "2_2") (pintype "passive"))
      (node (ref "U1") (pin "15") (pinfunction "PA1_15") (pintype "bidirectional"))
    )
    (net (code "38") (name "Net-(U1-PA2)") (class "Default")
      (node (ref "C12") (pin "2") (pinfunction "2_2") (pintype "passive"))
      (node (ref "R11") (pin "2") (pinfunction "2_2") (pintype "passive"))
      (node (ref "U1") (pin "16") (pinfunction "PA2_16") (pintype "bidirectional"))
    )
    (net (code "39") (name "Net-(U1-PA3)") (class "Default")
      (node (ref "C13") (pin "2") (pinfunction "2_2") (pintype "passive"))
      (node (ref "R12") (pin "2") (pinfunction "2_2") (pintype "passive"))
      (node (ref "U1") (pin "17") (pinfunction "PA3_17") (pintype "bidirectional"))
    )
    (net (code "40") (name "Net-(U1-VDDA)") (class "Default")
      (node (ref "C6") (pin "2") (pinfunction "2_2") (pintype "passive"))
      (node (ref "C7") (pin "2") (pinfunction "2_2") (pintype "passive"))
      (node (ref "L6") (pin "2") (pinfunction "2_2") (pintype "passive"))
      (node (ref "U1") (pin "13") (pinfunction "VDDA_13") (pintype "power_in"))
    )
    (net (code "41") (name "Net-(U2-BP)") (class "Default")
      (node (ref "C21") (pin "2") (pinfunction "2_2") (pintype "passive"))
      (node (ref "U2") (pin "4") (pinfunction "BP_4") (pintype "passive"))
    )
    (net (code "42") (name "Net-(U4-BST)") (class "Default")
      (node (ref "C19") (pin "1") (pinfunction "1_1") (pintype "passive"))
      (node (ref "U4") (pin "8") (pinfunction "BST_8") (pintype "passive"))
    )
    (net (code "43") (name "Net-(U4-COMP)") (class "Default")
      (node (ref "C18") (pin "1") (pinfunction "1_1") (pintype "passive"))
      (node (ref "U4") (pin "3") (pinfunction "COMP_3") (pintype "passive"))
    )
    (net (code "44") (name "Net-(U4-FB)") (class "Default")
      (node (ref "R20") (pin "1") (pinfunction "1_1") (pintype "passive"))
      (node (ref "R21") (pin "2") (pinfunction "2_2") (pintype "passive"))
      (node (ref "U4") (pin "4") (pinfunction "FB_4") (pintype "passive"))
    )
    (net (code "45") (name "Net-(U4-FREQ)") (class "Default")
      (node (ref "R19") (pin "2") (pinfunction "2_2") (pintype "passive"))
      (node (ref "U4") (pin "6") (pinfunction "FREQ_6") (pintype "passive"))
    )
    (net (code "46") (name "Net-(U5-RFO)") (class "Default")
      (node (ref "C15") (pin "1") (pinfunction "1_1") (pintype "passive"))
      (node (ref "L1") (pin "1") (pinfunction "1_1") (pintype "passive"))
      (node (ref "U5") (pin "5") (pinfunction "RFO_5") (pintype "passive"))
    )
    (net (code "47") (name "Net-(U5-XTAL)") (class "Default")
      (node (ref "U5") (pin "1") (pinfunction "XTAL_1") (pintype "passive"))
      (node (ref "X2") (pin "1") (pintype "passive"))
    )
    (net (code "48") (name "Net-(U10-+IN)") (class "Default")
      (node (ref "R15") (pin "1") (pinfunction "1_1") (pintype "passive"))
      (node (ref "U10") (pin "1") (pinfunction "+IN_1") (pintype "passive"))
      (node (ref "U9") (pin "4") (pinfunction "B_4") (pintype "passive"))
      (node (ref "U9") (pin "6") (pinfunction "B_6") (pintype "passive"))
    )
    (net (code "49") (name "Net-(U12-+IN)") (class "Default")
      (node (ref "R26") (pin "2") (pintype "passive"))
      (node (ref "U12") (pin "1") (pinfunction "+IN_1") (pintype "passive"))
    )
    (net (code "50") (name "Net-(U12--IN)") (class "Default")
      (node (ref "C27") (pin "2") (pinfunction "2_2") (pintype "passive"))
      (node (ref "R28") (pin "2") (pinfunction "2_2") (pintype "passive"))
      (node (ref "R29") (pin "1") (pinfunction "1_1") (pintype "passive"))
      (node (ref "U12") (pin "3") (pinfunction "-IN_3") (pintype "passive"))
    )
    (net (code "51") (name "Net-(U13-BP)") (class "Default")
      (node (ref "C41") (pin "2") (pinfunction "2_2") (pintype "passive"))
      (node (ref "U13") (pin "4") (pinfunction "BP_4") (pintype "passive"))
    )
    (net (code "52") (name "Net-(X1-OSC2)") (class "Default")
      (node (ref "R1") (pin "1") (pinfunction "1_1") (pintype "passive"))
      (node (ref "X1") (pin "3") (pinfunction "OSC2_3") (pintype "passive"))
    )
    (net (code "53") (name "unconnected-(DLOAD-D--Pad2)") (class "Default")
      (node (ref "DLOAD") (pin "2") (pinfunction "D-_2") (pintype "passive"))
    )
    (net (code "54") (name "unconnected-(U1-NRST-Pad7)") (class "Default")
      (node (ref "U1") (pin "7") (pinfunction "NRST_7") (pintype "bidirectional"))
    )
    (net (code "55") (name "unconnected-(U1-PA0-WKUP-Pad14)") (class "Default")
      (node (ref "U1") (pin "14") (pinfunction "PA0-WKUP_14") (pintype "bidirectional"))
    )
    (net (code "56") (name "unconnected-(U1-PA4-Pad20)") (class "Default")
      (node (ref "U1") (pin "20") (pinfunction "PA4_20") (pintype "bidirectional"))
    )
    (net (code "57") (name "unconnected-(U1-PA5-Pad21)") (class "Default")
      (node (ref "U1") (pin "21") (pinfunction "PA5_21") (pintype "bidirectional"))
    )
    (net (code "58") (name "unconnected-(U1-PA6-Pad22)") (class "Default")
      (node (ref "U1") (pin "22") (pinfunction "PA6_22") (pintype "bidirectional"))
    )
    (net (code "59") (name "unconnected-(U1-PA7-Pad23)") (class "Default")
      (node (ref "U1") (pin "23") (pinfunction "PA7_23") (pintype "bidirectional"))
    )
    (net (code "60") (name "unconnected-(U1-PA8-Pad41)") (class "Default")
      (node (ref "U1") (pin "41") (pinfunction "PA8_41") (pintype "bidirectional"))
    )
    (net (code "61") (name "unconnected-(U1-PA9-Pad42)") (class "Default")
      (node (ref "U1") (pin "42") (pinfunction "PA9_42") (pintype "bidirectional"))
    )
    (net (code "62") (name "unconnected-(U1-PA10-Pad43)") (class "Default")
      (node (ref "U1") (pin "43") (pinfunction "PA10_43") (pintype "bidirectional"))
    )
    (net (code "63") (name "unconnected-(U1-PA11-Pad44)") (class "Default")
      (node (ref "U1") (pin "44") (pinfunction "PA11_44") (pintype "bidirectional"))
    )
    (net (code "64") (name "unconnected-(U1-PA12-Pad45)") (class "Default")
      (node (ref "U1") (pin "45") (pinfunction "PA12_45") (pintype "bidirectional"))
    )
    (net (code "65") (name "unconnected-(U1-PA15{slash}JTDI-Pad50)") (class "Default")
      (node (ref "U1") (pin "50") (pinfunction "PA15/JTDI_50") (pintype "bidirectional"))
    )
    (net (code "66") (name "unconnected-(U1-PB2{slash}BOOT1-Pad28)") (class "Default")
      (node (ref "U1") (pin "28") (pinfunction "PB2/BOOT1_28") (pintype "bidirectional"))
    )
    (net (code "67") (name "unconnected-(U1-PB3{slash}JTDO-Pad55)") (class "Default")
      (node (ref "U1") (pin "55") (pinfunction "PB3/JTDO_55") (pintype "bidirectional"))
    )
    (net (code "68") (name "unconnected-(U1-PB4{slash}JNTRST-Pad56)") (class "Default")
      (node (ref "U1") (pin "56") (pinfunction "PB4/JNTRST_56") (pintype "bidirectional"))
    )
    (net (code "69") (name "unconnected-(U1-PB5-Pad57)") (class "Default")
      (node (ref "U1") (pin "57") (pinfunction "PB5_57") (pintype "bidirectional"))
    )
    (net (code "70") (name "unconnected-(U1-PB7-Pad59)") (class "Default")
      (node (ref "U1") (pin "59") (pinfunction "PB7_59") (pintype "bidirectional"))
    )
    (net (code "71") (name "unconnected-(U1-PB8-Pad61)") (class "Default")
      (node (ref "U1") (pin "61") (pinfunction "PB8_61") (pintype "bidirectional"))
    )
    (net (code "72") (name "unconnected-(U1-PB9-Pad62)") (class "Default")
      (node (ref "U1") (pin "62") (pinfunction "PB9_62") (pintype "bidirectional"))
    )
    (net (code "73") (name "unconnected-(U1-PB14-Pad35)") (class "Default")
      (node (ref "U1") (pin "35") (pinfunction "PB14_35") (pintype "bidirectional"))
    )
    (net (code "74") (name "unconnected-(U1-PB15-Pad36)") (class "Default")
      (node (ref "U1") (pin "36") (pinfunction "PB15_36") (pintype "bidirectional"))
    )
    (net (code "75") (name "unconnected-(U1-PC0-Pad8)") (class "Default")
      (node (ref "U1") (pin "8") (pinfunction "PC0_8") (pintype "bidirectional"))
    )
    (net (code "76") (name "unconnected-(U1-PC1-Pad9)") (class "Default")
      (node (ref "U1") (pin "9") (pinfunction "PC1_9") (pintype "bidirectional"))
    )
    (net (code "77") (name "unconnected-(U1-PC2-Pad10)") (class "Default")
      (node (ref "U1") (pin "10") (pinfunction "PC2_10") (pintype "bidirectional"))
    )
    (net (code "78") (name "unconnected-(U1-PC3-Pad11)") (class "Default")
      (node (ref "U1") (pin "11") (pinfunction "PC3_11") (pintype "bidirectional"))
    )
    (net (code "79") (name "unconnected-(U1-PC4-Pad24)") (class "Default")
      (node (ref "U1") (pin "24") (pinfunction "PC4_24") (pintype "bidirectional"))
    )
    (net (code "80") (name "unconnected-(U1-PC5-Pad25)") (class "Default")
      (node (ref "U1") (pin "25") (pinfunction "PC5_25") (pintype "bidirectional"))
    )
    (net (code "81") (name "unconnected-(U1-PC6-Pad37)") (class "Default")
      (node (ref "U1") (pin "37") (pinfunction "PC6_37") (pintype "bidirectional"))
    )
    (net (code "82") (name "unconnected-(U1-PC7-Pad38)") (class "Default")
      (node (ref "U1") (pin "38") (pinfunction "PC7_38") (pintype "bidirectional"))
    )
    (net (code "83") (name "unconnected-(U1-PC8-Pad39)") (class "Default")
      (node (ref "U1") (pin "39") (pinfunction "PC8_39") (pintype "bidirectional"))
    )
    (net (code "84") (name "unconnected-(U1-PC9-Pad40)") (class "Default")
      (node (ref "U1") (pin "40") (pinfunction "PC9_40") (pintype "bidirectional"))
    )
    (net (code "85") (name "unconnected-(U1-PC10-Pad51)") (class "Default")
      (node (ref "U1") (pin "51") (pinfunction "PC10_51") (pintype "bidirectional"))
    )
    (net (code "86") (name "unconnected-(U1-PC11-Pad52)") (class "Default")
      (node (ref "U1") (pin "52") (pinfunction "PC11_52") (pintype "bidirectional"))
    )
    (net (code "87") (name "unconnected-(U1-PC12-Pad53)") (class "Default")
      (node (ref "U1") (pin "53") (pinfunction "PC12_53") (pintype "bidirectional"))
    )
    (net (code "88") (name "unconnected-(U1-PC15-OSC32_OUT-Pad4)") (class "Default")
      (node (ref "U1") (pin "4") (pinfunction "PC15-OSC32_OUT_4") (pintype "bidirectional"))
    )
    (net (code "89") (name "unconnected-(U1-PD2-Pad54)") (class "Default")
      (node (ref "U1") (pin "54") (pinfunction "PD2_54") (pintype "bidirectional"))
    )
    (net (code "90") (name "unconnected-(U1-VBAT-Pad1)") (class "Default")
      (node (ref "U1") (pin "1") (pinfunction "VBAT_1") (pintype "power_in"))
    )
    (net (code "91") (name "unconnected-(U4-EN-Pad2)") (class "Default")
      (node (ref "U4") (pin "2") (pinfunction "EN_2") (pintype "passive"))
    )
    (net (code "92") (name "unconnected-(U8-NC-Pad3)") (class "Default")
      (node (ref "U8") (pin "3") (pinfunction "NC_3") (pintype "passive"))
    )
    (net (code "93") (name "unconnected-(U8-NC-Pad4)") (class "Default")
      (node (ref "U8") (pin "4") (pinfunction "NC_4") (pintype "passive"))
    )
  )
)
